# eMMC.net
KiCad netlist of a schematic drawn in Altium Designer
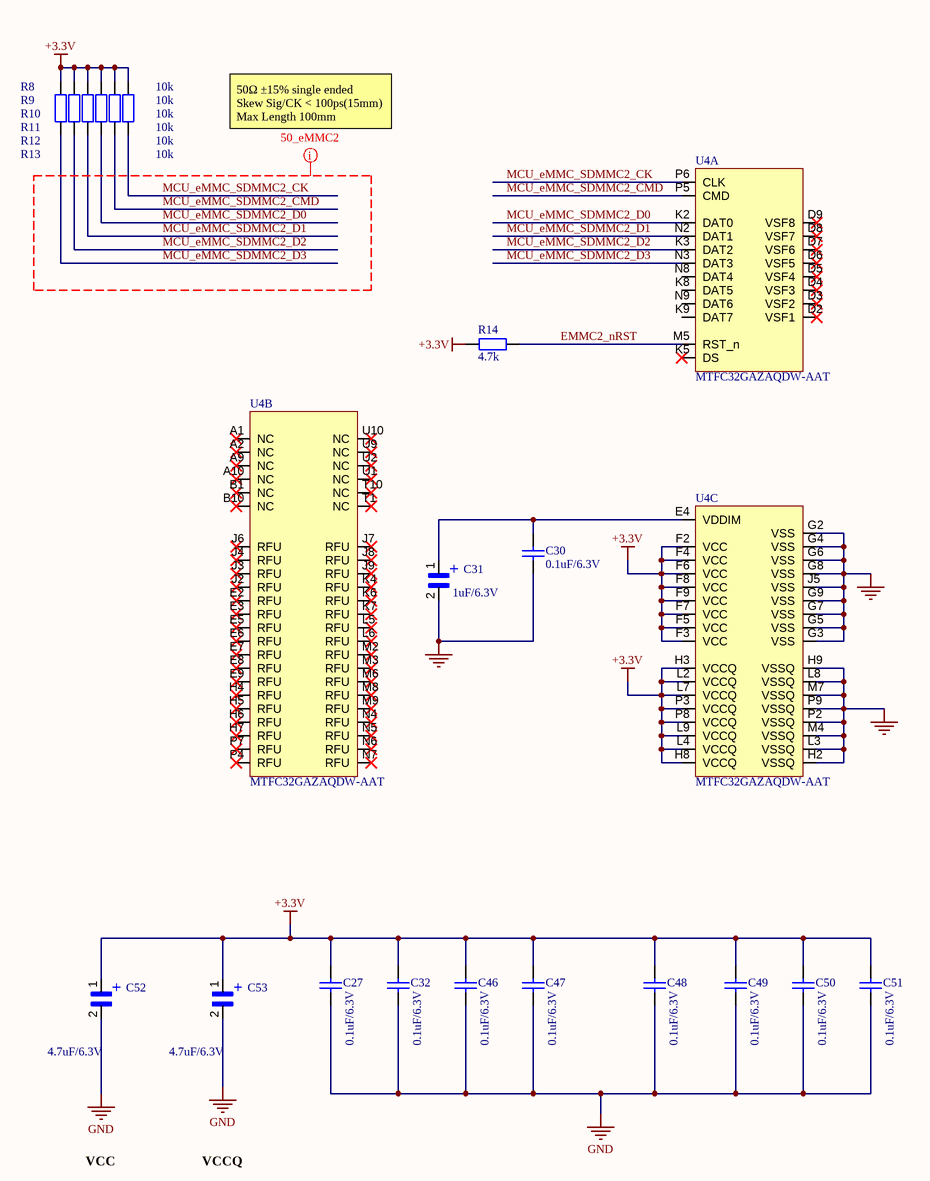
[diagram p0: eMMC.SchDoc]

(export (version "E")
  (design (tool "Eeschema 10.0.6"))
  (components
    (comp (ref "C27")
      (value "0.1uF/6.3V")
      (footprint "CAP_C_1608X80")
      (description "CAPC")
      (libsource (lib "Altium_Lib_by_KhueNguyenCreator") (part "Tu 0402 33nF 10V"))
    )
    (comp (ref "C30")
      (value "0.1uF/6.3V")
      (footprint "CAP_C_1608X80")
      (description "CAPC")
      (libsource (lib "Altium_Lib_by_KhueNguyenCreator") (part "Tu 0402 33nF 10V"))
    )
    (comp (ref "C31")
      (value "1uF/6.3V")
      (footprint "CAP_MP_1608X90")
      (description "CAPP")
      (fields (field (name "MP") "TACL335M003RTA"))
      (libsource (lib "TACL335M003RTA") (part "TACL335M003RTA"))
    )
    (comp (ref "C32")
      (value "0.1uF/6.3V")
      (footprint "CAP_C_1608X80")
      (description "CAPC")
      (libsource (lib "Altium_Lib_by_KhueNguyenCreator") (part "Tu 0402 33nF 10V"))
    )
    (comp (ref "C46")
      (value "0.1uF/6.3V")
      (footprint "CAP_C_1608X80")
      (description "CAPC")
      (libsource (lib "Altium_Lib_by_KhueNguyenCreator") (part "Tu 0402 33nF 10V"))
    )
    (comp (ref "C47")
      (value "0.1uF/6.3V")
      (footprint "CAP_C_1608X80")
      (description "CAPC")
      (libsource (lib "Altium_Lib_by_KhueNguyenCreator") (part "Tu 0402 33nF 10V"))
    )
    (comp (ref "C48")
      (value "0.1uF/6.3V")
      (footprint "CAP_C_1608X80")
      (description "CAPC")
      (libsource (lib "Altium_Lib_by_KhueNguyenCreator") (part "Tu 0402 33nF 10V"))
    )
    (comp (ref "C49")
      (value "0.1uF/6.3V")
      (footprint "CAP_C_1608X80")
      (description "CAPC")
      (libsource (lib "Altium_Lib_by_KhueNguyenCreator") (part "Tu 0402 33nF 10V"))
    )
    (comp (ref "C50")
      (value "0.1uF/6.3V")
      (footprint "CAP_C_1608X80")
      (description "CAPC")
      (libsource (lib "Altium_Lib_by_KhueNguyenCreator") (part "Tu 0402 33nF 10V"))
    )
    (comp (ref "C51")
      (value "0.1uF/6.3V")
      (footprint "CAP_C_1608X80")
      (description "CAPC")
      (libsource (lib "Altium_Lib_by_KhueNguyenCreator") (part "Tu 0402 33nF 10V"))
    )
    (comp (ref "C52")
      (value "4.7uF/6.3V")
      (footprint "CAP_MP_1608X90")
      (description "CAPP")
      (fields (field (name "MP") "TACL335M003RTA"))
      (libsource (lib "TACL335M003RTA") (part "TACL335M003RTA"))
    )
    (comp (ref "C53")
      (value "4.7uF/6.3V")
      (footprint "CAP_MP_1608X90")
      (description "CAPP")
      (fields (field (name "MP") "TACL335M003RTA"))
      (libsource (lib "TACL335M003RTA") (part "TACL335M003RTA"))
    )
    (comp (ref "R8")
      (value "10k")
      (footprint "RES_C_1608X60")
      (description "RES 4.7K OHM 1% 1/10W 0603, P/N: ERJ-U03F4701V")
      (libsource (lib "Altium_Lib_by_KhueNguyenCreator") (part "Tro 0603 1% 10k"))
    )
    (comp (ref "R9")
      (value "10k")
      (footprint "RES_C_1608X60")
      (description "RES 4.7K OHM 1% 1/10W 0603, P/N: ERJ-U03F4701V")
      (libsource (lib "Altium_Lib_by_KhueNguyenCreator") (part "Tro 0603 1% 10k"))
    )
    (comp (ref "R10")
      (value "10k")
      (footprint "RES_C_1608X60")
      (description "RES 4.7K OHM 1% 1/10W 0603, P/N: ERJ-U03F4701V")
      (libsource (lib "Altium_Lib_by_KhueNguyenCreator") (part "Tro 0603 1% 10k"))
    )
    (comp (ref "R11")
      (value "10k")
      (footprint "RES_C_1608X60")
      (description "RES 4.7K OHM 1% 1/10W 0603, P/N: ERJ-U03F4701V")
      (libsource (lib "Altium_Lib_by_KhueNguyenCreator") (part "Tro 0603 1% 10k"))
    )
    (comp (ref "R12")
      (value "10k")
      (footprint "RES_C_1608X60")
      (description "RES 4.7K OHM 1% 1/10W 0603, P/N: ERJ-U03F4701V")
      (libsource (lib "Altium_Lib_by_KhueNguyenCreator") (part "Tro 0603 1% 10k"))
    )
    (comp (ref "R13")
      (value "10k")
      (footprint "RES_C_1608X60")
      (description "RES 4.7K OHM 1% 1/10W 0603, P/N: ERJ-U03F4701V")
      (libsource (lib "Altium_Lib_by_KhueNguyenCreator") (part "Tro 0603 1% 10k"))
    )
    (comp (ref "R14")
      (value "4.7k")
      (footprint "RES_C_1608X60")
      (description "RES")
      (libsource (lib "Altium_Lib_by_KhueNguyenCreator") (part "Tro 0603 1% 10k"))
    )
    (comp (ref "U4")
      (value "MTFC32GAZAQDW-AAT")
      (footprint "BGA_100_C_100P_10X17_1400X1800X150")
      (libsource (lib "emmc_nofootprint") (part "MTFC32GAZAQDW-AAT"))
    )
  )
  (nets
    (net (code "1") (name "+3.3V") (class "Default")
      (node (ref "C27") (pin "1") (pinfunction "1_1") (pintype "passive"))
      (node (ref "C32") (pin "1") (pinfunction "1_1") (pintype "passive"))
      (node (ref "C46") (pin "1") (pinfunction "1_1") (pintype "passive"))
      (node (ref "C47") (pin "1") (pinfunction "1_1") (pintype "passive"))
      (node (ref "C48") (pin "1") (pinfunction "1_1") (pintype "passive"))
      (node (ref "C49") (pin "1") (pinfunction "1_1") (pintype "passive"))
      (node (ref "C50") (pin "1") (pinfunction "1_1") (pintype "passive"))
      (node (ref "C51") (pin "1") (pinfunction "1_1") (pintype "passive"))
      (node (ref "C52") (pin "1") (pinfunction "1_1") (pintype "passive"))
      (node (ref "C53") (pin "1") (pinfunction "1_1") (pintype "passive"))
      (node (ref "R10") (pin "2") (pinfunction "2_2") (pintype "passive"))
      (node (ref "R11") (pin "2") (pinfunction "2_2") (pintype "passive"))
      (node (ref "R12") (pin "2") (pinfunction "2_2") (pintype "passive"))
      (node (ref "R13") (pin "2") (pinfunction "2_2") (pintype "passive"))
      (node (ref "R14") (pin "1") (pinfunction "1_1") (pintype "passive"))
      (node (ref "R8") (pin "2") (pinfunction "2_2") (pintype "passive"))
      (node (ref "R9") (pin "2") (pinfunction "2_2") (pintype "passive"))
      (node (ref "U4") (pin "F2") (pinfunction "VCC_F2") (pintype "passive"))
      (node (ref "U4") (pin "F3") (pinfunction "VCC_F3") (pintype "passive"))
      (node (ref "U4") (pin "F4") (pinfunction "VCC_F4") (pintype "passive"))
      (node (ref "U4") (pin "F5") (pinfunction "VCC_F5") (pintype "passive"))
      (node (ref "U4") (pin "F6") (pinfunction "VCC_F6") (pintype "passive"))
      (node (ref "U4") (pin "F7") (pinfunction "VCC_F7") (pintype "passive"))
      (node (ref "U4") (pin "F8") (pinfunction "VCC_F8") (pintype "passive"))
      (node (ref "U4") (pin "F9") (pinfunction "VCC_F9") (pintype "passive"))
      (node (ref "U4") (pin "H3") (pinfunction "VCCQ_H3") (pintype "passive"))
      (node (ref "U4") (pin "H8") (pinfunction "VCCQ_H8") (pintype "passive"))
      (node (ref "U4") (pin "L2") (pinfunction "VCCQ_L2") (pintype "passive"))
      (node (ref "U4") (pin "L4") (pinfunction "VCCQ_L4") (pintype "passive"))
      (node (ref "U4") (pin "L7") (pinfunction "VCCQ_L7") (pintype "passive"))
      (node (ref "U4") (pin "L9") (pinfunction "VCCQ_L9") (pintype "passive"))
      (node (ref "U4") (pin "P3") (pinfunction "VCCQ_P3") (pintype "passive"))
      (node (ref "U4") (pin "P8") (pinfunction "VCCQ_P8") (pintype "passive"))
    )
    (net (code "2") (name "/EMMC2_nRST") (class "Default")
      (node (ref "R14") (pin "2") (pinfunction "2_2") (pintype "passive"))
      (node (ref "U4") (pin "M5") (pinfunction "RST_n_M5") (pintype "passive"))
    )
    (net (code "3") (name "/MCU_eMMC_SDMMC2_CK") (class "Default")
      (node (ref "R13") (pin "1") (pinfunction "1_1") (pintype "passive"))
      (node (ref "U4") (pin "P6") (pinfunction "CLK_P6") (pintype "passive"))
    )
    (net (code "4") (name "/MCU_eMMC_SDMMC2_CMD") (class "Default")
      (node (ref "R12") (pin "1") (pinfunction "1_1") (pintype "passive"))
      (node (ref "U4") (pin "P5") (pinfunction "CMD_P5") (pintype "passive"))
    )
    (net (code "5") (name "/MCU_eMMC_SDMMC2_D0") (class "Default")
      (node (ref "R11") (pin "1") (pinfunction "1_1") (pintype "passive"))
      (node (ref "U4") (pin "K2") (pinfunction "DAT0_K2") (pintype "passive"))
    )
    (net (code "6") (name "/MCU_eMMC_SDMMC2_D1") (class "Default")
      (node (ref "R10") (pin "1") (pinfunction "1_1") (pintype "passive"))
      (node (ref "U4") (pin "N2") (pinfunction "DAT1_N2") (pintype "passive"))
    )
    (net (code "7") (name "/MCU_eMMC_SDMMC2_D2") (class "Default")
      (node (ref "R9") (pin "1") (pinfunction "1_1") (pintype "passive"))
      (node (ref "U4") (pin "K3") (pinfunction "DAT2_K3") (pintype "passive"))
    )
    (net (code "8") (name "/MCU_eMMC_SDMMC2_D3") (class "Default")
      (node (ref "R8") (pin "1") (pinfunction "1_1") (pintype "passive"))
      (node (ref "U4") (pin "N3") (pinfunction "DAT3_N3") (pintype "passive"))
    )
    (net (code "9") (name "GND") (class "Default")
      (node (ref "C27") (pin "2") (pinfunction "2_2") (pintype "passive"))
      (node (ref "C30") (pin "2") (pinfunction "2_2") (pintype "passive"))
      (node (ref "C31") (pin "2") (pinfunction "2_2") (pintype "passive"))
      (node (ref "C32") (pin "2") (pinfunction "2_2") (pintype "passive"))
      (node (ref "C46") (pin "2") (pinfunction "2_2") (pintype "passive"))
      (node (ref "C47") (pin "2") (pinfunction "2_2") (pintype "passive"))
      (node (ref "C48") (pin "2") (pinfunction "2_2") (pintype "passive"))
      (node (ref "C49") (pin "2") (pinfunction "2_2") (pintype "passive"))
      (node (ref "C50") (pin "2") (pinfunction "2_2") (pintype "passive"))
      (node (ref "C51") (pin "2") (pinfunction "2_2") (pintype "passive"))
      (node (ref "C52") (pin "2") (pinfunction "2_2") (pintype "passive"))
      (node (ref "C53") (pin "2") (pinfunction "2_2") (pintype "passive"))
      (node (ref "U4") (pin "G2") (pinfunction "VSS_G2") (pintype "passive"))
      (node (ref "U4") (pin "G3") (pinfunction "VSS_G3") (pintype "passive"))
      (node (ref "U4") (pin "G4") (pinfunction "VSS_G4") (pintype "passive"))
      (node (ref "U4") (pin "G5") (pinfunction "VSS_G5") (pintype "passive"))
      (node (ref "U4") (pin "G6") (pinfunction "VSS_G6") (pintype "passive"))
      (node (ref "U4") (pin "G7") (pinfunction "VSS_G7") (pintype "passive"))
      (node (ref "U4") (pin "G8") (pinfunction "VSS_G8") (pintype "passive"))
      (node (ref "U4") (pin "G9") (pinfunction "VSS_G9") (pintype "passive"))
      (node (ref "U4") (pin "H2") (pinfunction "VSSQ_H2") (pintype "passive"))
      (node (ref "U4") (pin "H9") (pinfunction "VSSQ_H9") (pintype "passive"))
      (node (ref "U4") (pin "J5") (pinfunction "VSS_J5") (pintype "passive"))
      (node (ref "U4") (pin "L3") (pinfunction "VSSQ_L3") (pintype "passive"))
      (node (ref "U4") (pin "L8") (pinfunction "VSSQ_L8") (pintype "passive"))
      (node (ref "U4") (pin "M4") (pinfunction "VSSQ_M4") (pintype "passive"))
      (node (ref "U4") (pin "M7") (pinfunction "VSSQ_M7") (pintype "passive"))
      (node (ref "U4") (pin "P2") (pinfunction "VSSQ_P2") (pintype "passive"))
      (node (ref "U4") (pin "P9") (pinfunction "VSSQ_P9") (pintype "passive"))
    )
    (net (code "10") (name "Net-(U4C-VDDIM)") (class "Default")
      (node (ref "C30") (pin "1") (pinfunction "1_1") (pintype "passive"))
      (node (ref "C31") (pin "1") (pinfunction "1_1") (pintype "passive"))
      (node (ref "U4") (pin "E4") (pinfunction "VDDIM_E4") (pintype "passive"))
    )
    (net (code "11") (name "unconnected-(U4A-DAT4-PadN8)") (class "Default")
      (node (ref "U4") (pin "N8") (pinfunction "DAT4_N8") (pintype "passive"))
    )
    (net (code "12") (name "unconnected-(U4A-DAT5-PadK8)") (class "Default")
      (node (ref "U4") (pin "K8") (pinfunction "DAT5_K8") (pintype "passive"))
    )
    (net (code "13") (name "unconnected-(U4A-DAT6-PadN9)") (class "Default")
      (node (ref "U4") (pin "N9") (pinfunction "DAT6_N9") (pintype "passive"))
    )
    (net (code "14") (name "unconnected-(U4A-DAT7-PadK9)") (class "Default")
      (node (ref "U4") (pin "K9") (pinfunction "DAT7_K9") (pintype "passive"))
    )
    (net (code "15") (name "unconnected-(U4A-DS-PadK5)") (class "Default")
      (node (ref "U4") (pin "K5") (pinfunction "DS_K5") (pintype "passive+no_connect"))
    )
    (net (code "16") (name "unconnected-(U4A-VSF1-PadD2)") (class "Default")
      (node (ref "U4") (pin "D2") (pinfunction "VSF1_D2") (pintype "passive+no_connect"))
    )
    (net (code "17") (name "unconnected-(U4A-VSF2-PadD3)") (class "Default")
      (node (ref "U4") (pin "D3") (pinfunction "VSF2_D3") (pintype "passive+no_connect"))
    )
    (net (code "18") (name "unconnected-(U4A-VSF3-PadD4)") (class "Default")
      (node (ref "U4") (pin "D4") (pinfunction "VSF3_D4") (pintype "passive+no_connect"))
    )
    (net (code "19") (name "unconnected-(U4A-VSF4-PadD5)") (class "Default")
      (node (ref "U4") (pin "D5") (pinfunction "VSF4_D5") (pintype "passive+no_connect"))
    )
    (net (code "20") (name "unconnected-(U4A-VSF5-PadD6)") (class "Default")
      (node (ref "U4") (pin "D6") (pinfunction "VSF5_D6") (pintype "passive+no_connect"))
    )
    (net (code "21") (name "unconnected-(U4A-VSF6-PadD7)") (class "Default")
      (node (ref "U4") (pin "D7") (pinfunction "VSF6_D7") (pintype "passive+no_connect"))
    )
    (net (code "22") (name "unconnected-(U4A-VSF7-PadD8)") (class "Default")
      (node (ref "U4") (pin "D8") (pinfunction "VSF7_D8") (pintype "passive+no_connect"))
    )
    (net (code "23") (name "unconnected-(U4A-VSF8-PadD9)") (class "Default")
      (node (ref "U4") (pin "D9") (pinfunction "VSF8_D9") (pintype "passive+no_connect"))
    )
    (net (code "24") (name "unconnected-(U4B-NC-PadA1)") (class "Default")
      (node (ref "U4") (pin "A1") (pinfunction "NC_A1") (pintype "passive+no_connect"))
    )
    (net (code "25") (name "unconnected-(U4B-NC-PadA2)") (class "Default")
      (node (ref "U4") (pin "A2") (pinfunction "NC_A2") (pintype "passive+no_connect"))
    )
    (net (code "26") (name "unconnected-(U4B-NC-PadA9)") (class "Default")
      (node (ref "U4") (pin "A9") (pinfunction "NC_A9") (pintype "passive+no_connect"))
    )
    (net (code "27") (name "unconnected-(U4B-NC-PadA10)") (class "Default")
      (node (ref "U4") (pin "A10") (pinfunction "NC_A10") (pintype "passive+no_connect"))
    )
    (net (code "28") (name "unconnected-(U4B-NC-PadB1)") (class "Default")
      (node (ref "U4") (pin "B1") (pinfunction "NC_B1") (pintype "passive+no_connect"))
    )
    (net (code "29") (name "unconnected-(U4B-NC-PadB10)") (class "Default")
      (node (ref "U4") (pin "B10") (pinfunction "NC_B10") (pintype "passive+no_connect"))
    )
    (net (code "30") (name "unconnected-(U4B-NC-PadT1)") (class "Default")
      (node (ref "U4") (pin "T1") (pinfunction "NC_T1") (pintype "passive+no_connect"))
    )
    (net (code "31") (name "unconnected-(U4B-NC-PadT10)") (class "Default")
      (node (ref "U4") (pin "T10") (pinfunction "NC_T10") (pintype "passive+no_connect"))
    )
    (net (code "32") (name "unconnected-(U4B-NC-PadU1)") (class "Default")
      (node (ref "U4") (pin "U1") (pinfunction "NC_U1") (pintype "passive+no_connect"))
    )
    (net (code "33") (name "unconnected-(U4B-NC-PadU2)") (class "Default")
      (node (ref "U4") (pin "U2") (pinfunction "NC_U2") (pintype "passive+no_connect"))
    )
    (net (code "34") (name "unconnected-(U4B-NC-PadU9)") (class "Default")
      (node (ref "U4") (pin "U9") (pinfunction "NC_U9") (pintype "passive+no_connect"))
    )
    (net (code "35") (name "unconnected-(U4B-NC-PadU10)") (class "Default")
      (node (ref "U4") (pin "U10") (pinfunction "NC_U10") (pintype "passive+no_connect"))
    )
    (net (code "36") (name "unconnected-(U4B-RFU-PadE2)") (class "Default")
      (node (ref "U4") (pin "E2") (pinfunction "RFU_E2") (pintype "passive+no_connect"))
    )
    (net (code "37") (name "unconnected-(U4B-RFU-PadE3)") (class "Default")
      (node (ref "U4") (pin "E3") (pinfunction "RFU_E3") (pintype "passive+no_connect"))
    )
    (net (code "38") (name "unconnected-(U4B-RFU-PadE5)") (class "Default")
      (node (ref "U4") (pin "E5") (pinfunction "RFU_E5") (pintype "passive+no_connect"))
    )
    (net (code "39") (name "unconnected-(U4B-RFU-PadE6)") (class "Default")
      (node (ref "U4") (pin "E6") (pinfunction "RFU_E6") (pintype "passive+no_connect"))
    )
    (net (code "40") (name "unconnected-(U4B-RFU-PadE7)") (class "Default")
      (node (ref "U4") (pin "E7") (pinfunction "RFU_E7") (pintype "passive+no_connect"))
    )
    (net (code "41") (name "unconnected-(U4B-RFU-PadE8)") (class "Default")
      (node (ref "U4") (pin "E8") (pinfunction "RFU_E8") (pintype "passive+no_connect"))
    )
    (net (code "42") (name "unconnected-(U4B-RFU-PadE9)") (class "Default")
      (node (ref "U4") (pin "E9") (pinfunction "RFU_E9") (pintype "passive+no_connect"))
    )
    (net (code "43") (name "unconnected-(U4B-RFU-PadH4)") (class "Default")
      (node (ref "U4") (pin "H4") (pinfunction "RFU_H4") (pintype "passive+no_connect"))
    )
    (net (code "44") (name "unconnected-(U4B-RFU-PadH5)") (class "Default")
      (node (ref "U4") (pin "H5") (pinfunction "RFU_H5") (pintype "passive+no_connect"))
    )
    (net (code "45") (name "unconnected-(U4B-RFU-PadH6)") (class "Default")
      (node (ref "U4") (pin "H6") (pinfunction "RFU_H6") (pintype "passive+no_connect"))
    )
    (net (code "46") (name "unconnected-(U4B-RFU-PadH7)") (class "Default")
      (node (ref "U4") (pin "H7") (pinfunction "RFU_H7") (pintype "passive+no_connect"))
    )
    (net (code "47") (name "unconnected-(U4B-RFU-PadJ2)") (class "Default")
      (node (ref "U4") (pin "J2") (pinfunction "RFU_J2") (pintype "passive+no_connect"))
    )
    (net (code "48") (name "unconnected-(U4B-RFU-PadJ3)") (class "Default")
      (node (ref "U4") (pin "J3") (pinfunction "RFU_J3") (pintype "passive+no_connect"))
    )
    (net (code "49") (name "unconnected-(U4B-RFU-PadJ4)") (class "Default")
      (node (ref "U4") (pin "J4") (pinfunction "RFU_J4") (pintype "passive+no_connect"))
    )
    (net (code "50") (name "unconnected-(U4B-RFU-PadJ6)") (class "Default")
      (node (ref "U4") (pin "J6") (pinfunction "RFU_J6") (pintype "passive+no_connect"))
    )
    (net (code "51") (name "unconnected-(U4B-RFU-PadJ7)") (class "Default")
      (node (ref "U4") (pin "J7") (pinfunction "RFU_J7") (pintype "passive+no_connect"))
    )
    (net (code "52") (name "unconnected-(U4B-RFU-PadJ8)") (class "Default")
      (node (ref "U4") (pin "J8") (pinfunction "RFU_J8") (pintype "passive+no_connect"))
    )
    (net (code "53") (name "unconnected-(U4B-RFU-PadJ9)") (class "Default")
      (node (ref "U4") (pin "J9") (pinfunction "RFU_J9") (pintype "passive+no_connect"))
    )
    (net (code "54") (name "unconnected-(U4B-RFU-PadK4)") (class "Default")
      (node (ref "U4") (pin "K4") (pinfunction "RFU_K4") (pintype "passive+no_connect"))
    )
    (net (code "55") (name "unconnected-(U4B-RFU-PadK6)") (class "Default")
      (node (ref "U4") (pin "K6") (pinfunction "RFU_K6") (pintype "passive+no_connect"))
    )
    (net (code "56") (name "unconnected-(U4B-RFU-PadK7)") (class "Default")
      (node (ref "U4") (pin "K7") (pinfunction "RFU_K7") (pintype "passive+no_connect"))
    )
    (net (code "57") (name "unconnected-(U4B-RFU-PadL5)") (class "Default")
      (node (ref "U4") (pin "L5") (pinfunction "RFU_L5") (pintype "passive+no_connect"))
    )
    (net (code "58") (name "unconnected-(U4B-RFU-PadL6)") (class "Default")
      (node (ref "U4") (pin "L6") (pinfunction "RFU_L6") (pintype "passive+no_connect"))
    )
    (net (code "59") (name "unconnected-(U4B-RFU-PadM2)") (class "Default")
      (node (ref "U4") (pin "M2") (pinfunction "RFU_M2") (pintype "passive+no_connect"))
    )
    (net (code "60") (name "unconnected-(U4B-RFU-PadM3)") (class "Default")
      (node (ref "U4") (pin "M3") (pinfunction "RFU_M3") (pintype "passive+no_connect"))
    )
    (net (code "61") (name "unconnected-(U4B-RFU-PadM6)") (class "Default")
      (node (ref "U4") (pin "M6") (pinfunction "RFU_M6") (pintype "passive+no_connect"))
    )
    (net (code "62") (name "unconnected-(U4B-RFU-PadM8)") (class "Default")
      (node (ref "U4") (pin "M8") (pinfunction "RFU_M8") (pintype "passive+no_connect"))
    )
    (net (code "63") (name "unconnected-(U4B-RFU-PadM9)") (class "Default")
      (node (ref "U4") (pin "M9") (pinfunction "RFU_M9") (pintype "passive+no_connect"))
    )
    (net (code "64") (name "unconnected-(U4B-RFU-PadN4)") (class "Default")
      (node (ref "U4") (pin "N4") (pinfunction "RFU_N4") (pintype "passive+no_connect"))
    )
    (net (code "65") (name "unconnected-(U4B-RFU-PadN5)") (class "Default")
      (node (ref "U4") (pin "N5") (pinfunction "RFU_N5") (pintype "passive+no_connect"))
    )
    (net (code "66") (name "unconnected-(U4B-RFU-PadN6)") (class "Default")
      (node (ref "U4") (pin "N6") (pinfunction "RFU_N6") (pintype "passive+no_connect"))
    )
    (net (code "67") (name "unconnected-(U4B-RFU-PadN7)") (class "Default")
      (node (ref "U4") (pin "N7") (pinfunction "RFU_N7") (pintype "passive+no_connect"))
    )
    (net (code "68") (name "unconnected-(U4B-RFU-PadP4)") (class "Default")
      (node (ref "U4") (pin "P4") (pinfunction "RFU_P4") (pintype "passive+no_connect"))
    )
    (net (code "69") (name "unconnected-(U4B-RFU-PadP7)") (class "Default")
      (node (ref "U4") (pin "P7") (pinfunction "RFU_P7") (pintype "passive+no_connect"))
    )
  )
)
